# LEDLightRing.net
KiCad netlist of a schematic drawn in Altium Designer
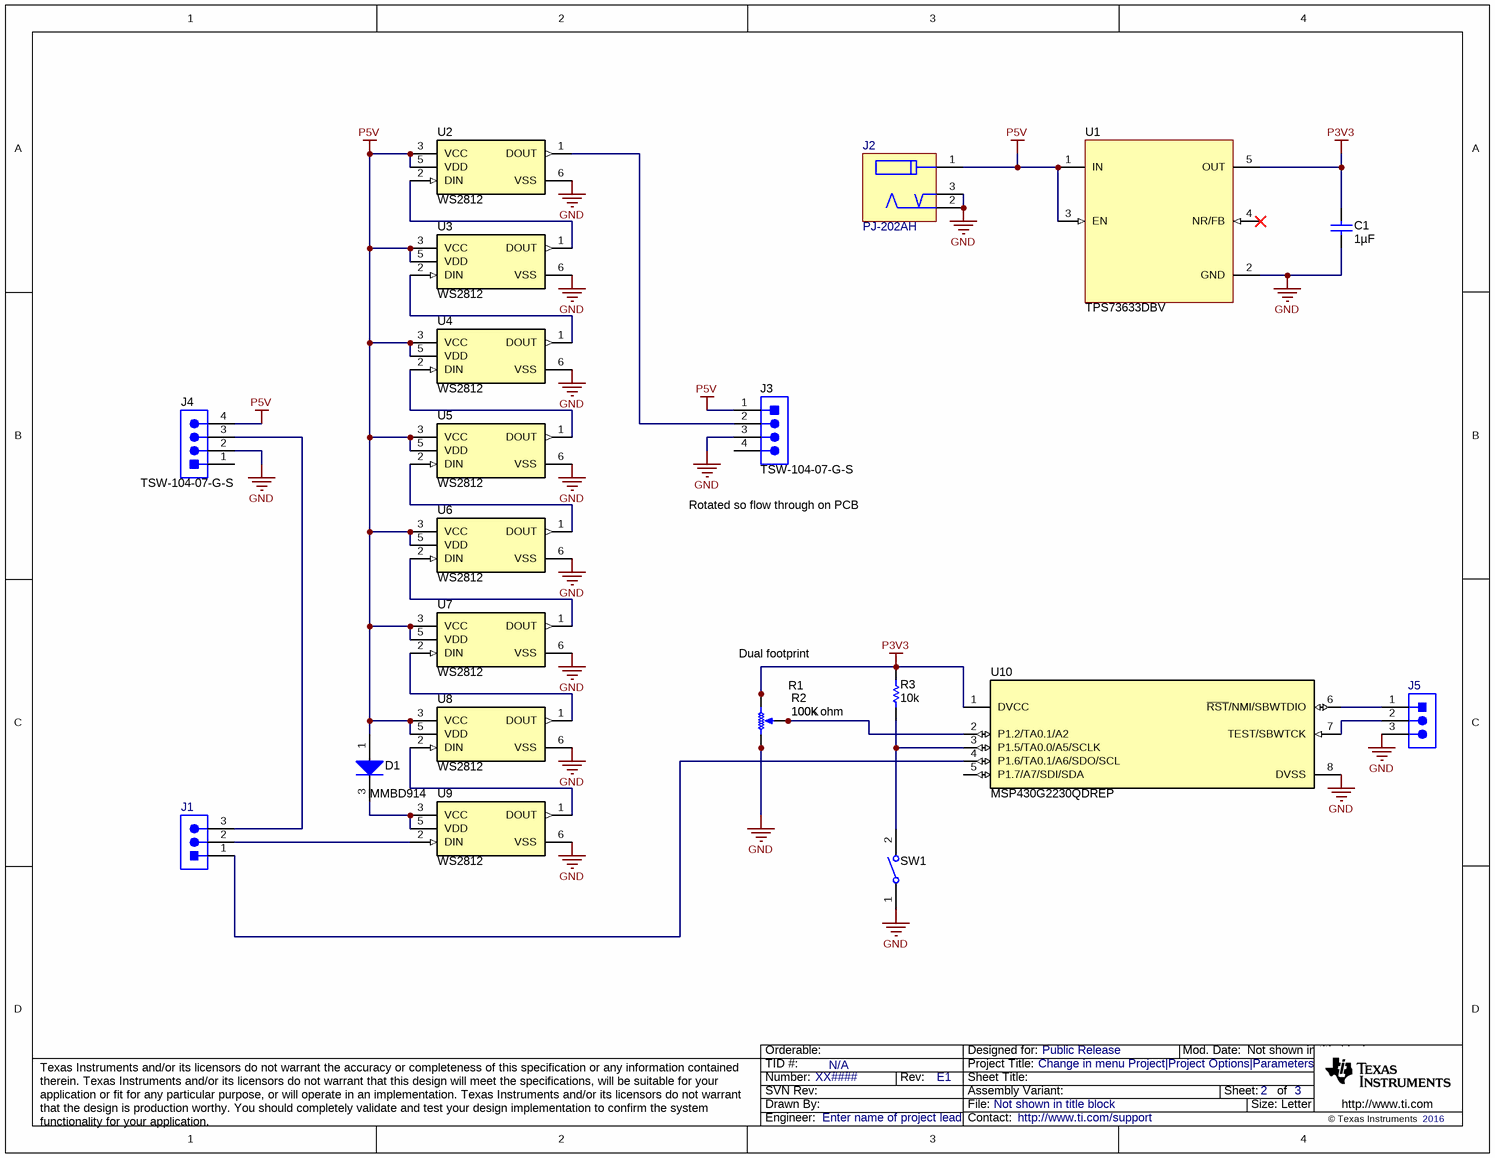
[diagram p0: LEDLightRing.SchDoc]

(export (version "E")
  (design (tool "Eeschema 10.0.6"))
  (components
    (comp (ref "C1")
      (value "UMK107AB7105KA-T")
      (footprint "0603")
      (description "CAP, CERM, 1 µF, 50 V, +/- 10%, X7R, 0603")
      (fields
        (field (name "VALUEDISPLAYED") "1µF")
        (field (name "MANUFACTURER") "Taiyo Yuden")
        (field (name "PUBLISHER") "Texas Instruments")
      )
      (libsource (lib "Capacitor_Ceramic") (part "UMK107AB7105KA-T"))
    )
    (comp (ref "D1")
      (value "MMBD914")
      (footprint "SOT-23")
      (description "Diode, P-N, 100 V, 0.2 A, SOT-23")
      (fields
        (field (name "MANUFACTURER") "Fairchild Semiconductor")
        (field (name "PUBLISHER") "Texas Instruments")
      )
      (libsource (lib "Diode") (part "MMBD914"))
    )
    (comp (ref "J1")
      (value "TSW-103-07-T-S")
      (footprint "Samtec_TSW-103-07-T-S")
      (description "Header, 2.54 mm, 3x1, Tin, TH")
      (fields
        (field (name "MANUFACTURER") "Samtec")
        (field (name "SYMBOLCREATOR") "a0799628")
        (field (name "PUBLISHER") "Texas Instruments")
      )
      (libsource (lib "Connectors_Samtec") (part "TSW-103-07-T-S"))
    )
    (comp (ref "J2")
      (value "PJ-202AH")
      (footprint "CONN_CUI-PJ-202AH")
      (description "Connector, DC Jack 2.1X5.5 mm, TH")
      (fields
        (field (name "MANUFACTURER") "CUI Inc.")
        (field (name "SYMBOLCREATOR") "a0799628")
        (field (name "PUBLISHER") "Texas Instruments")
      )
      (libsource (lib "Connectors_Other") (part "PJ-202AH"))
    )
    (comp (ref "J3")
      (value "TSW-104-07-G-S")
      (footprint "TSW-104-07-G-S")
      (description "Header, 100mil, 4x1, Gold, TH")
      (fields
        (field (name "MANUFACTURER") "Samtec")
        (field (name "SYMBOLCREATOR") "a0412235")
        (field (name "PUBLISHER") "Texas Instruments")
      )
      (libsource (lib "Connectors_Samtec") (part "TSW-104-07-G-S"))
    )
    (comp (ref "J4")
      (value "TSW-104-07-G-S")
      (footprint "TSW-104-07-G-S")
      (description "Header, 100mil, 4x1, Gold, TH")
      (fields
        (field (name "MANUFACTURER") "Samtec")
        (field (name "SYMBOLCREATOR") "a0412235")
        (field (name "PUBLISHER") "Texas Instruments")
      )
      (libsource (lib "") (part "TSW-104-07-G-S_1"))
    )
    (comp (ref "J5")
      (value "TSW-103-07-T-S")
      (footprint "Samtec_TSW-103-07-T-S")
      (description "Header, 2.54 mm, 3x1, Tin, TH")
      (fields
        (field (name "MANUFACTURER") "Samtec")
        (field (name "SYMBOLCREATOR") "a0799628")
        (field (name "PUBLISHER") "Texas Instruments")
      )
      (libsource (lib "") (part "TSW-103-07-T-S_1"))
    )
    (comp (ref "R1")
      (value "100K")
      (footprint "CTS_296UD")
      (description "Trimmer, 100k ohms, 0.15 W, TH")
      (fields
        (field (name "PARTNUMBER") "296UD104B1N")
        (field (name "MANUFACTURER") "CTS Electrocomponents")
        (field (name "SYMBOLCREATOR") "a0412235")
        (field (name "PUBLISHER") "Texas Instruments")
      )
      (libsource (lib "Other_Passive") (part "296UD104B1N"))
    )
    (comp (ref "R2")
      (value "100k ohm")
      (footprint "Bourns_3386F-T")
      (description "TRIMMER 100K OHM 0.5W, TH")
      (fields
        (field (name "PARTNUMBER") "3386F-1-104TLF")
        (field (name "MANUFACTURER") "Bourns")
        (field (name "SYMBOLCREATOR") "a0412235")
        (field (name "PUBLISHER") "Texas Instruments")
      )
      (libsource (lib "Other_Passive") (part "3386F-1-103TLF"))
    )
    (comp (ref "R3")
      (value "CRCW060310K0JNEA")
      (footprint "0603")
      (description "RES, 10 k, 5%, 0.1 W, 0603")
      (fields
        (field (name "VALUEDISPLAYED") "10k")
        (field (name "MANUFACTURER") "Vishay-Dale")
        (field (name "PUBLISHER") "Texas Instruments")
      )
      (libsource (lib "Resistor_0603") (part "CRCW060310K0JNEA"))
    )
    (comp (ref "SW1")
      (value "RS-032G05A3-SM RT")
      (footprint "SW_RS-032G05A3-SM")
      (description "Switch, Tactile, SPST-NO, 0.05A, 12V, SMD")
      (fields
        (field (name "MANUFACTURER") "C&K Components")
        (field (name "SYMBOLCREATOR") "a0799628")
        (field (name "PUBLISHER") "Texas Instruments")
      )
      (libsource (lib "Switches") (part "RS-032G05A3-SM RT"))
    )
    (comp (ref "U1")
      (value "TPS73633DBV")
      (footprint "DBV0005A_N")
      (description "Cap-Free, NMOS, 400mA Low-Dropout Regulator with Reverse Current Protection, DBV0005A")
      (fields
        (field (name "MANUFACTURER") "Texas Instruments")
        (field (name "SYMBOLCREATOR") "a0411947")
        (field (name "PUBLISHER") "Texas Instruments")
      )
      (libsource (lib "TI_Pre_Release") (part "TPS73633DBV"))
    )
    (comp (ref "U2")
      (value "WS2812")
      (footprint "WS2812")
      (description "Intelligent Control LED Integrated Light Source")
      (fields
        (field (name "MANUFACTURER") "Hanwei Electronics")
        (field (name "SYMBOLCREATOR") "Altium")
        (field (name "PUBLISHER") "Texas Instruments")
      )
      (libsource (lib "LEDLightRing") (part "WS2812"))
    )
    (comp (ref "U3")
      (value "WS2812")
      (footprint "WS2812")
      (description "Intelligent Control LED Integrated Light Source")
      (fields
        (field (name "MANUFACTURER") "Hanwei Electronics")
        (field (name "SYMBOLCREATOR") "Altium")
        (field (name "PUBLISHER") "Texas Instruments")
      )
      (libsource (lib "LEDLightRing") (part "WS2812"))
    )
    (comp (ref "U4")
      (value "WS2812")
      (footprint "WS2812")
      (description "Intelligent Control LED Integrated Light Source")
      (fields
        (field (name "MANUFACTURER") "Hanwei Electronics")
        (field (name "SYMBOLCREATOR") "Altium")
        (field (name "PUBLISHER") "Texas Instruments")
      )
      (libsource (lib "LEDLightRing") (part "WS2812"))
    )
    (comp (ref "U5")
      (value "WS2812")
      (footprint "WS2812")
      (description "Intelligent Control LED Integrated Light Source")
      (fields
        (field (name "MANUFACTURER") "Hanwei Electronics")
        (field (name "SYMBOLCREATOR") "Altium")
        (field (name "PUBLISHER") "Texas Instruments")
      )
      (libsource (lib "LEDLightRing") (part "WS2812"))
    )
    (comp (ref "U6")
      (value "WS2812")
      (footprint "WS2812")
      (description "Intelligent Control LED Integrated Light Source")
      (fields
        (field (name "MANUFACTURER") "Hanwei Electronics")
        (field (name "SYMBOLCREATOR") "Altium")
        (field (name "PUBLISHER") "Texas Instruments")
      )
      (libsource (lib "LEDLightRing") (part "WS2812"))
    )
    (comp (ref "U7")
      (value "WS2812")
      (footprint "WS2812")
      (description "Intelligent Control LED Integrated Light Source")
      (fields
        (field (name "MANUFACTURER") "Hanwei Electronics")
        (field (name "SYMBOLCREATOR") "Altium")
        (field (name "PUBLISHER") "Texas Instruments")
      )
      (libsource (lib "LEDLightRing") (part "WS2812"))
    )
    (comp (ref "U8")
      (value "WS2812")
      (footprint "WS2812")
      (description "Intelligent Control LED Integrated Light Source")
      (fields
        (field (name "MANUFACTURER") "Hanwei Electronics")
        (field (name "SYMBOLCREATOR") "Altium")
        (field (name "PUBLISHER") "Texas Instruments")
      )
      (libsource (lib "LEDLightRing") (part "WS2812"))
    )
    (comp (ref "U9")
      (value "WS2812")
      (footprint "WS2812")
      (description "Intelligent Control LED Integrated Light Source")
      (fields
        (field (name "MANUFACTURER") "Hanwei Electronics")
        (field (name "SYMBOLCREATOR") "Altium")
        (field (name "PUBLISHER") "Texas Instruments")
      )
      (libsource (lib "LEDLightRing") (part "WS2812"))
    )
    (comp (ref "U10")
      (value "MSP430G2230QDREP")
      (footprint "D0008A_M")
      (fields
        (field (name "ALTERNATE PARTNUMBER") "MSP430G2230QDEP")
        (field (name "MANUFACTURER") "Texas Instruments")
        (field (name "SYMBOLCREATOR") "Altium")
        (field (name "PUBLISHER") "Texas Instruments")
      )
      (libsource (lib "TI_Pre_Release1") (part "MSP430G2230QDREP"))
    )
  )
  (nets
    (net (code "1") (name "GND") (class "Default")
      (node (ref "C1") (pin "2") (pinfunction "2_2") (pintype "passive"))
      (node (ref "J2") (pin "2") (pinfunction "2_2") (pintype "passive"))
      (node (ref "J2") (pin "3") (pinfunction "3_3") (pintype "passive"))
      (node (ref "J3") (pin "3") (pinfunction "3_3") (pintype "passive"))
      (node (ref "J4") (pin "2") (pinfunction "2_2") (pintype "passive"))
      (node (ref "J5") (pin "3") (pinfunction "3_3") (pintype "passive"))
      (node (ref "R1") (pin "3") (pinfunction "CW_3") (pintype "passive"))
      (node (ref "R2") (pin "1") (pinfunction "CCW_1") (pintype "passive"))
      (node (ref "SW1") (pin "1") (pinfunction "1_1") (pintype "passive"))
      (node (ref "U1") (pin "2") (pinfunction "GND_2") (pintype "power_in"))
      (node (ref "U10") (pin "8") (pinfunction "DVSS_8") (pintype "power_in"))
      (node (ref "U2") (pin "6") (pinfunction "VSS_6") (pintype "power_in"))
      (node (ref "U3") (pin "6") (pinfunction "VSS_6") (pintype "power_in"))
      (node (ref "U4") (pin "6") (pinfunction "VSS_6") (pintype "power_in"))
      (node (ref "U5") (pin "6") (pinfunction "VSS_6") (pintype "power_in"))
      (node (ref "U6") (pin "6") (pinfunction "VSS_6") (pintype "power_in"))
      (node (ref "U7") (pin "6") (pinfunction "VSS_6") (pintype "power_in"))
      (node (ref "U8") (pin "6") (pinfunction "VSS_6") (pintype "power_in"))
      (node (ref "U9") (pin "6") (pinfunction "VSS_6") (pintype "power_in"))
    )
    (net (code "2") (name "Net-(D1-K)") (class "Default")
      (node (ref "D1") (pin "3") (pinfunction "K_3") (pintype "passive"))
      (node (ref "U9") (pin "3") (pinfunction "VCC_3") (pintype "power_in"))
      (node (ref "U9") (pin "5") (pinfunction "VDD_5") (pintype "power_in"))
    )
    (net (code "3") (name "Net-(J1-Pad3)") (class "Default")
      (node (ref "J1") (pin "3") (pinfunction "3_3") (pintype "passive"))
      (node (ref "J4") (pin "3") (pinfunction "3_3") (pintype "passive"))
    )
    (net (code "4") (name "Net-(R1-WIPER)") (class "Default")
      (node (ref "R1") (pin "2") (pinfunction "WIPER_2") (pintype "passive"))
      (node (ref "R2") (pin "2") (pinfunction "WIPER_2") (pintype "passive"))
      (node (ref "U10") (pin "2") (pinfunction "P1.2/TA0.1/A2_2") (pintype "bidirectional"))
    )
    (net (code "5") (name "Net-(U2-DIN)") (class "Default")
      (node (ref "U2") (pin "2") (pinfunction "DIN_2") (pintype "input"))
      (node (ref "U3") (pin "1") (pinfunction "DOUT_1") (pintype "output"))
    )
    (net (code "6") (name "Net-(U2-DOUT)") (class "Default")
      (node (ref "J3") (pin "2") (pinfunction "2_2") (pintype "passive"))
      (node (ref "U2") (pin "1") (pinfunction "DOUT_1") (pintype "output"))
    )
    (net (code "7") (name "Net-(U3-DIN)") (class "Default")
      (node (ref "U3") (pin "2") (pinfunction "DIN_2") (pintype "input"))
      (node (ref "U4") (pin "1") (pinfunction "DOUT_1") (pintype "output"))
    )
    (net (code "8") (name "Net-(U4-DIN)") (class "Default")
      (node (ref "U4") (pin "2") (pinfunction "DIN_2") (pintype "input"))
      (node (ref "U5") (pin "1") (pinfunction "DOUT_1") (pintype "output"))
    )
    (net (code "9") (name "Net-(U5-DIN)") (class "Default")
      (node (ref "U5") (pin "2") (pinfunction "DIN_2") (pintype "input"))
      (node (ref "U6") (pin "1") (pinfunction "DOUT_1") (pintype "output"))
    )
    (net (code "10") (name "Net-(U6-DIN)") (class "Default")
      (node (ref "U6") (pin "2") (pinfunction "DIN_2") (pintype "input"))
      (node (ref "U7") (pin "1") (pinfunction "DOUT_1") (pintype "output"))
    )
    (net (code "11") (name "Net-(U7-DIN)") (class "Default")
      (node (ref "U7") (pin "2") (pinfunction "DIN_2") (pintype "input"))
      (node (ref "U8") (pin "1") (pinfunction "DOUT_1") (pintype "output"))
    )
    (net (code "12") (name "Net-(U8-DIN)") (class "Default")
      (node (ref "U8") (pin "2") (pinfunction "DIN_2") (pintype "input"))
      (node (ref "U9") (pin "1") (pinfunction "DOUT_1") (pintype "output"))
    )
    (net (code "13") (name "Net-(U9-DIN)") (class "Default")
      (node (ref "J1") (pin "2") (pinfunction "2_2") (pintype "passive"))
      (node (ref "U9") (pin "2") (pinfunction "DIN_2") (pintype "input"))
    )
    (net (code "14") (name "Net-(U10-P1.5{slash}TA0.0{slash}A5{slash}SCLK)") (class "Default")
      (node (ref "R3") (pin "2") (pinfunction "2_2") (pintype "passive"))
      (node (ref "SW1") (pin "2") (pinfunction "2_2") (pintype "passive"))
      (node (ref "U10") (pin "3") (pinfunction "P1.5/TA0.0/A5/SCLK_3") (pintype "bidirectional"))
    )
    (net (code "15") (name "Net-(U10-P1.6{slash}TA0.1{slash}A6{slash}SDO{slash}SCL)") (class "Default")
      (node (ref "J1") (pin "1") (pinfunction "1_1") (pintype "passive"))
      (node (ref "U10") (pin "4") (pinfunction "P1.6/TA0.1/A6/SDO/SCL_4") (pintype "bidirectional"))
    )
    (net (code "16") (name "Net-(U10-TEST{slash}SBWTCK)") (class "Default")
      (node (ref "J5") (pin "2") (pinfunction "2_2") (pintype "passive"))
      (node (ref "U10") (pin "7") (pinfunction "TEST/SBWTCK_7") (pintype "input"))
    )
    (net (code "17") (name "Net-(U10-~{RST}{slash}NMI{slash}SBWTDIO)") (class "Default")
      (node (ref "J5") (pin "1") (pinfunction "1_1") (pintype "passive"))
      (node (ref "U10") (pin "6") (pinfunction "~{RST}/NMI/SBWTDIO_6") (pintype "bidirectional"))
    )
    (net (code "18") (name "P3V3") (class "Default")
      (node (ref "C1") (pin "1") (pinfunction "1_1") (pintype "passive"))
      (node (ref "R1") (pin "1") (pinfunction "CCW_1") (pintype "passive"))
      (node (ref "R2") (pin "3") (pinfunction "CW_3") (pintype "passive"))
      (node (ref "R3") (pin "1") (pinfunction "1_1") (pintype "passive"))
      (node (ref "U1") (pin "5") (pinfunction "OUT_5") (pintype "power_in"))
      (node (ref "U10") (pin "1") (pinfunction "DVCC_1") (pintype "power_in"))
    )
    (net (code "19") (name "P5V") (class "Default")
      (node (ref "D1") (pin "1") (pinfunction "A_1") (pintype "passive"))
      (node (ref "J2") (pin "1") (pinfunction "1_1") (pintype "passive"))
      (node (ref "J3") (pin "1") (pinfunction "1_1") (pintype "passive"))
      (node (ref "J4") (pin "4") (pinfunction "4_4") (pintype "passive"))
      (node (ref "U1") (pin "1") (pinfunction "IN_1") (pintype "power_in"))
      (node (ref "U1") (pin "3") (pinfunction "EN_3") (pintype "input"))
      (node (ref "U2") (pin "3") (pinfunction "VCC_3") (pintype "power_in"))
      (node (ref "U2") (pin "5") (pinfunction "VDD_5") (pintype "power_in"))
      (node (ref "U3") (pin "3") (pinfunction "VCC_3") (pintype "power_in"))
      (node (ref "U3") (pin "5") (pinfunction "VDD_5") (pintype "power_in"))
      (node (ref "U4") (pin "3") (pinfunction "VCC_3") (pintype "power_in"))
      (node (ref "U4") (pin "5") (pinfunction "VDD_5") (pintype "power_in"))
      (node (ref "U5") (pin "3") (pinfunction "VCC_3") (pintype "power_in"))
      (node (ref "U5") (pin "5") (pinfunction "VDD_5") (pintype "power_in"))
      (node (ref "U6") (pin "3") (pinfunction "VCC_3") (pintype "power_in"))
      (node (ref "U6") (pin "5") (pinfunction "VDD_5") (pintype "power_in"))
      (node (ref "U7") (pin "3") (pinfunction "VCC_3") (pintype "power_in"))
      (node (ref "U7") (pin "5") (pinfunction "VDD_5") (pintype "power_in"))
      (node (ref "U8") (pin "3") (pinfunction "VCC_3") (pintype "power_in"))
      (node (ref "U8") (pin "5") (pinfunction "VDD_5") (pintype "power_in"))
    )
    (net (code "20") (name "unconnected-(J3-Pad4)") (class "Default")
      (node (ref "J3") (pin "4") (pinfunction "4_4") (pintype "passive"))
    )
    (net (code "21") (name "unconnected-(J4-Pad1)") (class "Default")
      (node (ref "J4") (pin "1") (pinfunction "1_1") (pintype "passive"))
    )
    (net (code "22") (name "unconnected-(U1-NR{slash}FB-Pad4)") (class "Default")
      (node (ref "U1") (pin "4") (pinfunction "NR/FB_4") (pintype "input+no_connect"))
    )
    (net (code "23") (name "unconnected-(U10-P1.7{slash}A7{slash}SDI{slash}SDA-Pad5)") (class "Default")
      (node (ref "U10") (pin "5") (pinfunction "P1.7/A7/SDI/SDA_5") (pintype "bidirectional"))
    )
  )
)
